# Time_Base_Generator.net
KiCad netlist of a schematic drawn in EAGLE
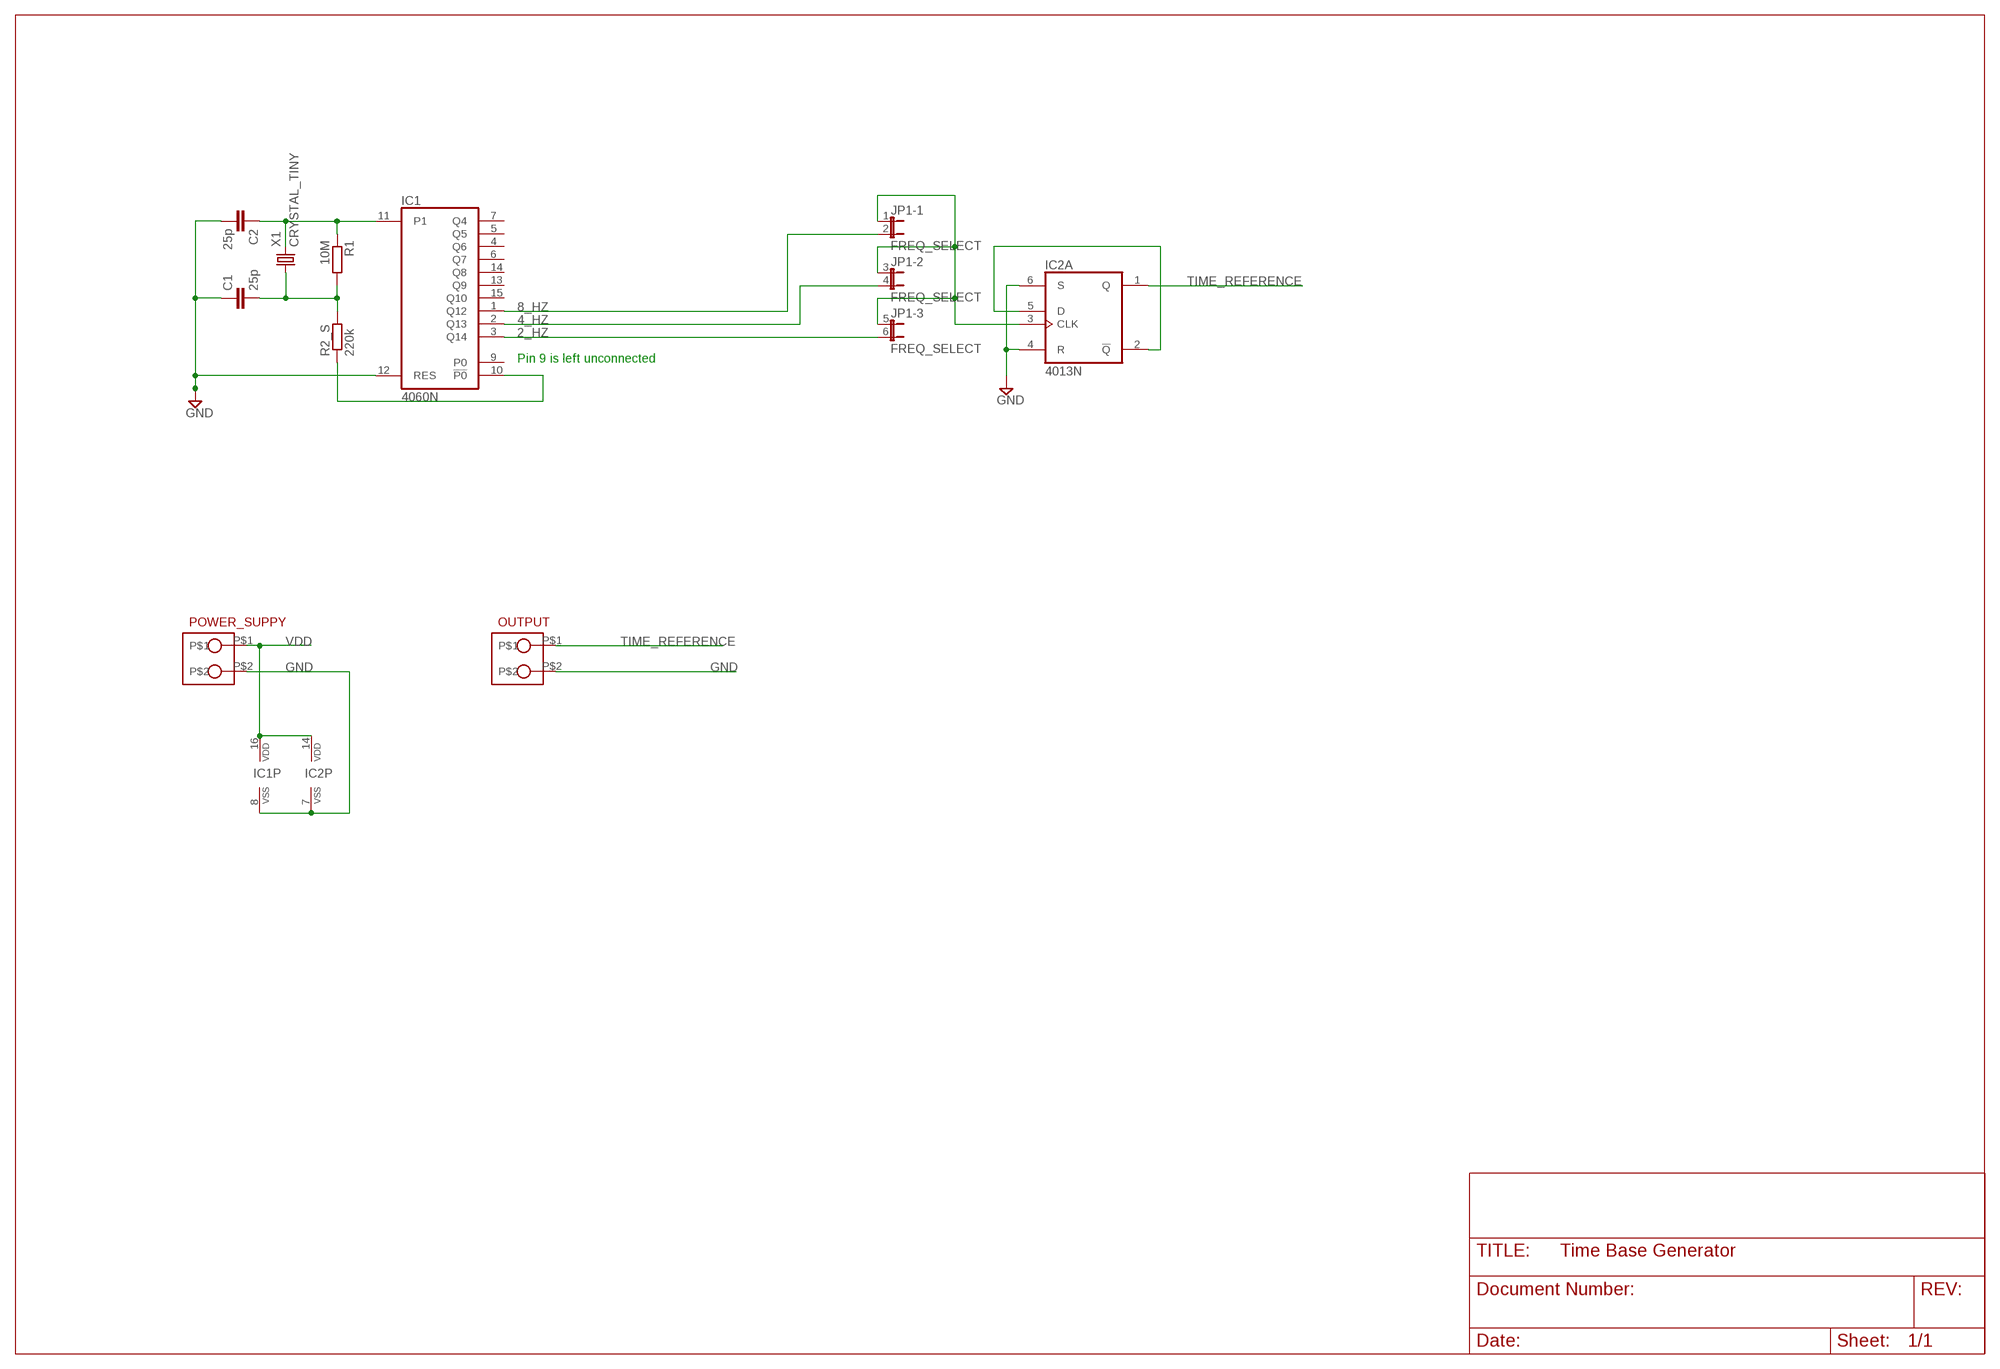
[diagram p0: schematic, sheet 1]

(export (version "E")
  (design (tool "Eeschema 10.0.6"))
  (components
    (comp (ref "C1")
      (value "25p")
      (footprint "eagle-import:C050-025X075")
      (libsource (lib "eagle-import") (part "C-EU050-025X075"))
    )
    (comp (ref "C2")
      (value "25p")
      (footprint "eagle-import:C050-025X075")
      (libsource (lib "eagle-import") (part "C-EU050-025X075"))
    )
    (comp (ref "IC1")
      (value "4060N")
      (footprint "eagle-import:DIL16")
      (libsource (lib "eagle-import") (part "4060N"))
    )
    (comp (ref "IC2")
      (value "4013N")
      (footprint "eagle-import:DIL14")
      (libsource (lib "eagle-import") (part "4013N"))
    )
    (comp (ref "JP1")
      (value "FREQ_SELECT")
      (footprint "eagle-import:JP3Q")
      (libsource (lib "eagle-import") (part "JP3QE"))
    )
    (comp (ref "OUTPUT")
      (value "CON_2_SIL")
      (footprint "eagle-import:SIL_2_0.2INCH")
      (libsource (lib "eagle-import") (part "CON_2_SIL"))
    )
    (comp (ref "POWER_SUPPY")
      (value "CON_2_SIL")
      (footprint "eagle-import:SIL_2_0.2INCH")
      (libsource (lib "eagle-import") (part "CON_2_SIL"))
    )
    (comp (ref "R1")
      (value "10M")
      (footprint "eagle-import:0207_10")
      (libsource (lib "eagle-import") (part "R-EU_0207/10"))
    )
    (comp (ref "R2_S")
      (value "220k")
      (footprint "eagle-import:0207_10")
      (libsource (lib "eagle-import") (part "R-EU_0207/10"))
    )
    (comp (ref "X1")
      (value "CRYSTAL_TINY")
      (footprint "eagle-import:WATCH-3X8-SPACED")
      (libsource (lib "eagle-import") (part "CRYSTAL_TINY"))
    )
  )
  (nets
    (net (code "1") (name "/2_HZ") (class "Default")
      (node (ref "IC1") (pin "3") (pinfunction "Q14_3") (pintype "output"))
      (node (ref "JP1") (pin "6") (pinfunction "2_6") (pintype "passive"))
    )
    (net (code "2") (name "/4_HZ") (class "Default")
      (node (ref "IC1") (pin "2") (pinfunction "Q13_2") (pintype "output"))
      (node (ref "JP1") (pin "4") (pinfunction "2_4") (pintype "passive"))
    )
    (net (code "3") (name "/8_HZ") (class "Default")
      (node (ref "IC1") (pin "1") (pinfunction "Q12_1") (pintype "output"))
      (node (ref "JP1") (pin "2") (pinfunction "2_2") (pintype "passive"))
    )
    (net (code "4") (name "/TIME_REFERENCE") (class "Default")
      (node (ref "IC2") (pin "1") (pinfunction "Q_1") (pintype "output"))
      (node (ref "OUTPUT") (pin "P$1") (pinfunction "P$1_P$1") (pintype "bidirectional"))
    )
    (net (code "5") (name "/VDD") (class "Default")
      (node (ref "IC1") (pin "16") (pinfunction "VDD_16") (pintype "power_in"))
      (node (ref "IC2") (pin "14") (pinfunction "VDD_14") (pintype "power_in"))
      (node (ref "POWER_SUPPY") (pin "P$1") (pinfunction "P$1_P$1") (pintype "bidirectional"))
    )
    (net (code "6") (name "GND") (class "Default")
      (node (ref "C1") (pin "1") (pinfunction "1_1") (pintype "passive"))
      (node (ref "C2") (pin "2") (pinfunction "2_2") (pintype "passive"))
      (node (ref "IC1") (pin "12") (pinfunction "RES_12") (pintype "input"))
      (node (ref "IC1") (pin "8") (pinfunction "VSS_8") (pintype "power_in"))
      (node (ref "IC2") (pin "4") (pinfunction "R_4") (pintype "input"))
      (node (ref "IC2") (pin "6") (pinfunction "S_6") (pintype "input"))
      (node (ref "IC2") (pin "7") (pinfunction "VSS_7") (pintype "power_in"))
      (node (ref "OUTPUT") (pin "P$2") (pinfunction "P$2_P$2") (pintype "bidirectional"))
      (node (ref "POWER_SUPPY") (pin "P$2") (pinfunction "P$2_P$2") (pintype "bidirectional"))
    )
    (net (code "7") (name "Net-(C1-Pad2)") (class "Default")
      (node (ref "C1") (pin "2") (pinfunction "2_2") (pintype "passive"))
      (node (ref "R1") (pin "2") (pinfunction "2_2") (pintype "passive"))
      (node (ref "R2_S") (pin "2") (pinfunction "2_2") (pintype "passive"))
      (node (ref "X1") (pin "1") (pinfunction "1_1") (pintype "passive"))
    )
    (net (code "8") (name "Net-(IC1A-P1)") (class "Default")
      (node (ref "C2") (pin "1") (pinfunction "1_1") (pintype "passive"))
      (node (ref "IC1") (pin "11") (pinfunction "P1_11") (pintype "input"))
      (node (ref "R1") (pin "1") (pinfunction "1_1") (pintype "passive"))
      (node (ref "X1") (pin "2") (pinfunction "2_2") (pintype "passive"))
    )
    (net (code "9") (name "Net-(IC1A-~{P0})") (class "Default")
      (node (ref "IC1") (pin "10") (pinfunction "~{P0}_10") (pintype "output"))
      (node (ref "R2_S") (pin "1") (pinfunction "1_1") (pintype "passive"))
    )
    (net (code "10") (name "Net-(IC2A-CLK)") (class "Default")
      (node (ref "IC2") (pin "3") (pinfunction "CLK_3") (pintype "input"))
      (node (ref "JP1") (pin "1") (pinfunction "1_1") (pintype "passive"))
      (node (ref "JP1") (pin "3") (pinfunction "1_3") (pintype "passive"))
      (node (ref "JP1") (pin "5") (pinfunction "1_5") (pintype "passive"))
    )
    (net (code "11") (name "Net-(IC2A-D)") (class "Default")
      (node (ref "IC2") (pin "2") (pinfunction "~{Q}_2") (pintype "output"))
      (node (ref "IC2") (pin "5") (pinfunction "D_5") (pintype "input"))
    )
    (net (code "12") (name "unconnected-(IC1A-P0-Pad9)") (class "Default")
      (node (ref "IC1") (pin "9") (pinfunction "P0_9") (pintype "output"))
    )
    (net (code "13") (name "unconnected-(IC1A-Q4-Pad7)") (class "Default")
      (node (ref "IC1") (pin "7") (pinfunction "Q4_7") (pintype "output"))
    )
    (net (code "14") (name "unconnected-(IC1A-Q5-Pad5)") (class "Default")
      (node (ref "IC1") (pin "5") (pinfunction "Q5_5") (pintype "output"))
    )
    (net (code "15") (name "unconnected-(IC1A-Q6-Pad4)") (class "Default")
      (node (ref "IC1") (pin "4") (pinfunction "Q6_4") (pintype "output"))
    )
    (net (code "16") (name "unconnected-(IC1A-Q7-Pad6)") (class "Default")
      (node (ref "IC1") (pin "6") (pinfunction "Q7_6") (pintype "output"))
    )
    (net (code "17") (name "unconnected-(IC1A-Q8-Pad14)") (class "Default")
      (node (ref "IC1") (pin "14") (pinfunction "Q8_14") (pintype "output"))
    )
    (net (code "18") (name "unconnected-(IC1A-Q9-Pad13)") (class "Default")
      (node (ref "IC1") (pin "13") (pinfunction "Q9_13") (pintype "output"))
    )
    (net (code "19") (name "unconnected-(IC1A-Q10-Pad15)") (class "Default")
      (node (ref "IC1") (pin "15") (pinfunction "Q10_15") (pintype "output"))
    )
  )
)
